# 4_USB-HS.net
KiCad netlist of a schematic drawn in Altium Designer
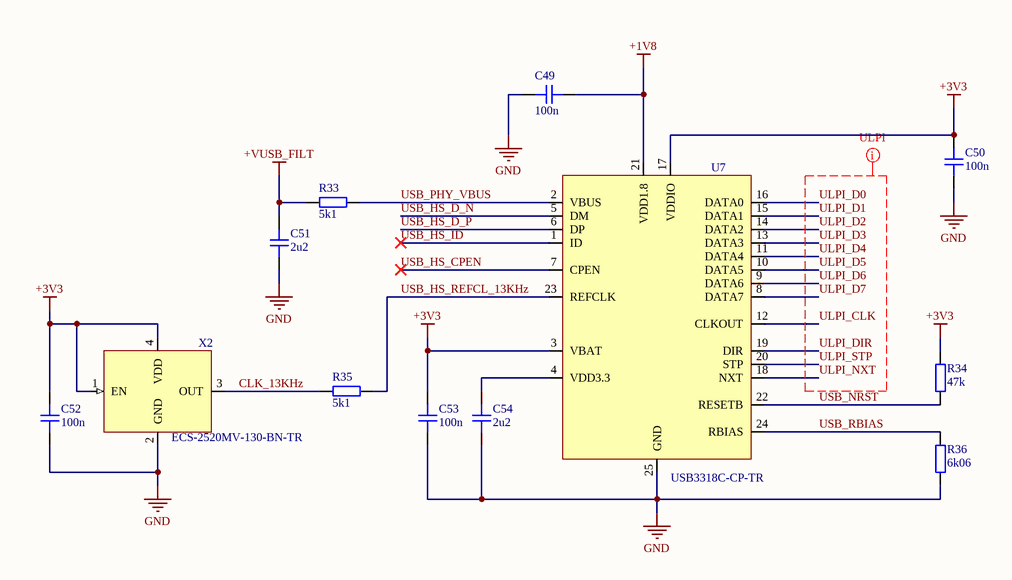
[diagram p0: 4_USB-HS.SchDoc]

(export (version "E")
  (design (tool "Eeschema 10.0.6"))
  (components
    (comp (ref "C49")
      (value "100n")
      (footprint "CAP_0201")
      (description "Capacitor SMD 0201")
      (libsource (lib "Schematic-Lib-PhilsLab") (part "CAP_0201"))
    )
    (comp (ref "C50")
      (value "100n")
      (footprint "CAP_0201")
      (description "Capacitor SMD 0201")
      (libsource (lib "Schematic-Lib-PhilsLab") (part "CAP_0201"))
    )
    (comp (ref "C51")
      (value "2u2")
      (footprint "CAP_0201")
      (description "Capacitor SMD 0201")
      (libsource (lib "Schematic-Lib-PhilsLab") (part "CAP_0201"))
    )
    (comp (ref "C52")
      (value "100n")
      (footprint "CAP_0201")
      (description "Capacitor SMD 0201")
      (libsource (lib "Schematic-Lib-PhilsLab") (part "CAP_0201"))
    )
    (comp (ref "C53")
      (value "100n")
      (footprint "CAP_0201")
      (description "Capacitor SMD 0201")
      (libsource (lib "Schematic-Lib-PhilsLab") (part "CAP_0201"))
    )
    (comp (ref "C54")
      (value "2u2")
      (footprint "CAP_0201")
      (description "Capacitor SMD 0201")
      (libsource (lib "Schematic-Lib-PhilsLab") (part "CAP_0201"))
    )
    (comp (ref "R33")
      (value "5k1")
      (footprint "RES_0402")
      (description "Resistor SMD 0402")
      (libsource (lib "Schematic-Lib-PhilsLab") (part "RES_0402"))
    )
    (comp (ref "R34")
      (value "47k")
      (footprint "RES_0402")
      (description "Resistor SMD 0402")
      (libsource (lib "Schematic-Lib-PhilsLab") (part "RES_0402"))
    )
    (comp (ref "R35")
      (value "5k1")
      (footprint "RES_0402")
      (description "Resistor SMD 0402")
      (libsource (lib "Schematic-Lib-PhilsLab") (part "RES_0402"))
    )
    (comp (ref "R36")
      (value "6k06")
      (footprint "RES_0402")
      (description "Resistor SMD 0402")
      (libsource (lib "Schematic-Lib-PhilsLab") (part "RES_0402"))
    )
    (comp (ref "U7")
      (value "USB3318C-CP-TR")
      (footprint "USB3318C-CP-TR")
      (description "USB Interface IC High Speed USB 1.8V ULPI")
      (fields (field (name "MANUFACTURER") "Microchip"))
      (libsource (lib "Schematic-Lib-PhilsLab") (part "USB3318C-CP-TR"))
    )
    (comp (ref "X2")
      (value "ECS-2520MV-130-BN-TR")
      (footprint "XTAL_2520")
      (fields (field (name "MANUFACTURER") "ECS"))
      (libsource (lib "Schematic-Lib-PhilsLab") (part "ECS-2520MV-130-BN-TR"))
    )
  )
  (nets
    (net (code "1") (name "+1V8") (class "Default")
      (node (ref "C49") (pin "2") (pinfunction "2_2") (pintype "passive"))
      (node (ref "U7") (pin "21") (pinfunction "VDD1.8_21") (pintype "passive"))
    )
    (net (code "2") (name "+3V3") (class "Default")
      (node (ref "C50") (pin "2") (pinfunction "2_2") (pintype "passive"))
      (node (ref "C52") (pin "2") (pinfunction "2_2") (pintype "passive"))
      (node (ref "C53") (pin "2") (pinfunction "2_2") (pintype "passive"))
      (node (ref "R34") (pin "2") (pinfunction "2_2") (pintype "passive"))
      (node (ref "U7") (pin "17") (pinfunction "VDDIO_17") (pintype "passive"))
      (node (ref "U7") (pin "3") (pinfunction "VBAT_3") (pintype "passive"))
      (node (ref "X2") (pin "1") (pinfunction "EN_1") (pintype "input"))
      (node (ref "X2") (pin "4") (pinfunction "VDD_4") (pintype "power_in"))
    )
    (net (code "3") (name "+VUSB_FILT") (class "Default")
      (node (ref "C51") (pin "2") (pinfunction "2_2") (pintype "passive"))
      (node (ref "R33") (pin "2") (pinfunction "2_2") (pintype "passive"))
    )
    (net (code "4") (name "/CLK_13KHz") (class "Default")
      (node (ref "R35") (pin "2") (pinfunction "2_2") (pintype "passive"))
      (node (ref "X2") (pin "3") (pinfunction "OUT_3") (pintype "passive"))
    )
    (net (code "5") (name "/ULPI_CLK") (class "Default")
      (node (ref "U7") (pin "12") (pinfunction "CLKOUT_12") (pintype "passive"))
    )
    (net (code "6") (name "/ULPI_D0") (class "Default")
      (node (ref "U7") (pin "16") (pinfunction "DATA0_16") (pintype "passive"))
    )
    (net (code "7") (name "/ULPI_D1") (class "Default")
      (node (ref "U7") (pin "15") (pinfunction "DATA1_15") (pintype "passive"))
    )
    (net (code "8") (name "/ULPI_D2") (class "Default")
      (node (ref "U7") (pin "14") (pinfunction "DATA2_14") (pintype "passive"))
    )
    (net (code "9") (name "/ULPI_D3") (class "Default")
      (node (ref "U7") (pin "13") (pinfunction "DATA3_13") (pintype "passive"))
    )
    (net (code "10") (name "/ULPI_D4") (class "Default")
      (node (ref "U7") (pin "11") (pinfunction "DATA4_11") (pintype "passive"))
    )
    (net (code "11") (name "/ULPI_D5") (class "Default")
      (node (ref "U7") (pin "10") (pinfunction "DATA5_10") (pintype "passive"))
    )
    (net (code "12") (name "/ULPI_D6") (class "Default")
      (node (ref "U7") (pin "9") (pinfunction "DATA6_9") (pintype "passive"))
    )
    (net (code "13") (name "/ULPI_D7") (class "Default")
      (node (ref "U7") (pin "8") (pinfunction "DATA7_8") (pintype "passive"))
    )
    (net (code "14") (name "/ULPI_DIR") (class "Default")
      (node (ref "U7") (pin "19") (pinfunction "DIR_19") (pintype "passive"))
    )
    (net (code "15") (name "/ULPI_NXT") (class "Default")
      (node (ref "U7") (pin "18") (pinfunction "NXT_18") (pintype "passive"))
    )
    (net (code "16") (name "/ULPI_STP") (class "Default")
      (node (ref "U7") (pin "20") (pinfunction "STP_20") (pintype "passive"))
    )
    (net (code "17") (name "/USB_HS_CPEN") (class "Default")
      (node (ref "U7") (pin "7") (pinfunction "CPEN_7") (pintype "passive+no_connect"))
    )
    (net (code "18") (name "/USB_HS_D_N") (class "Default")
      (node (ref "U7") (pin "5") (pinfunction "DM_5") (pintype "passive"))
    )
    (net (code "19") (name "/USB_HS_D_P") (class "Default")
      (node (ref "U7") (pin "6") (pinfunction "DP_6") (pintype "passive"))
    )
    (net (code "20") (name "/USB_HS_ID") (class "Default")
      (node (ref "U7") (pin "1") (pinfunction "ID_1") (pintype "passive+no_connect"))
    )
    (net (code "21") (name "/USB_HS_REFCL_13KHz") (class "Default")
      (node (ref "R35") (pin "1") (pinfunction "1_1") (pintype "passive"))
      (node (ref "U7") (pin "23") (pinfunction "REFCLK_23") (pintype "passive"))
    )
    (net (code "22") (name "/USB_NRST") (class "Default")
      (node (ref "R34") (pin "1") (pinfunction "1_1") (pintype "passive"))
      (node (ref "U7") (pin "22") (pinfunction "RESETB_22") (pintype "passive"))
    )
    (net (code "23") (name "/USB_PHY_VBUS") (class "Default")
      (node (ref "R33") (pin "1") (pinfunction "1_1") (pintype "passive"))
      (node (ref "U7") (pin "2") (pinfunction "VBUS_2") (pintype "passive"))
    )
    (net (code "24") (name "/USB_RBIAS") (class "Default")
      (node (ref "R36") (pin "2") (pinfunction "2_2") (pintype "passive"))
      (node (ref "U7") (pin "24") (pinfunction "RBIAS_24") (pintype "passive"))
    )
    (net (code "25") (name "GND") (class "Default")
      (node (ref "C49") (pin "1") (pinfunction "1_1") (pintype "passive"))
      (node (ref "C50") (pin "1") (pinfunction "1_1") (pintype "passive"))
      (node (ref "C51") (pin "1") (pinfunction "1_1") (pintype "passive"))
      (node (ref "C52") (pin "1") (pinfunction "1_1") (pintype "passive"))
      (node (ref "C53") (pin "1") (pinfunction "1_1") (pintype "passive"))
      (node (ref "C54") (pin "1") (pinfunction "1_1") (pintype "passive"))
      (node (ref "R36") (pin "1") (pinfunction "1_1") (pintype "passive"))
      (node (ref "U7") (pin "25") (pinfunction "GND_25") (pintype "passive"))
      (node (ref "X2") (pin "2") (pinfunction "GND_2") (pintype "power_in"))
    )
    (net (code "26") (name "Net-(U7-VDD3.3)") (class "Default")
      (node (ref "C54") (pin "2") (pinfunction "2_2") (pintype "passive"))
      (node (ref "U7") (pin "4") (pinfunction "VDD3.3_4") (pintype "passive"))
    )
  )
)
